# ETHERNET.net
KiCad netlist of a schematic drawn in Altium Designer
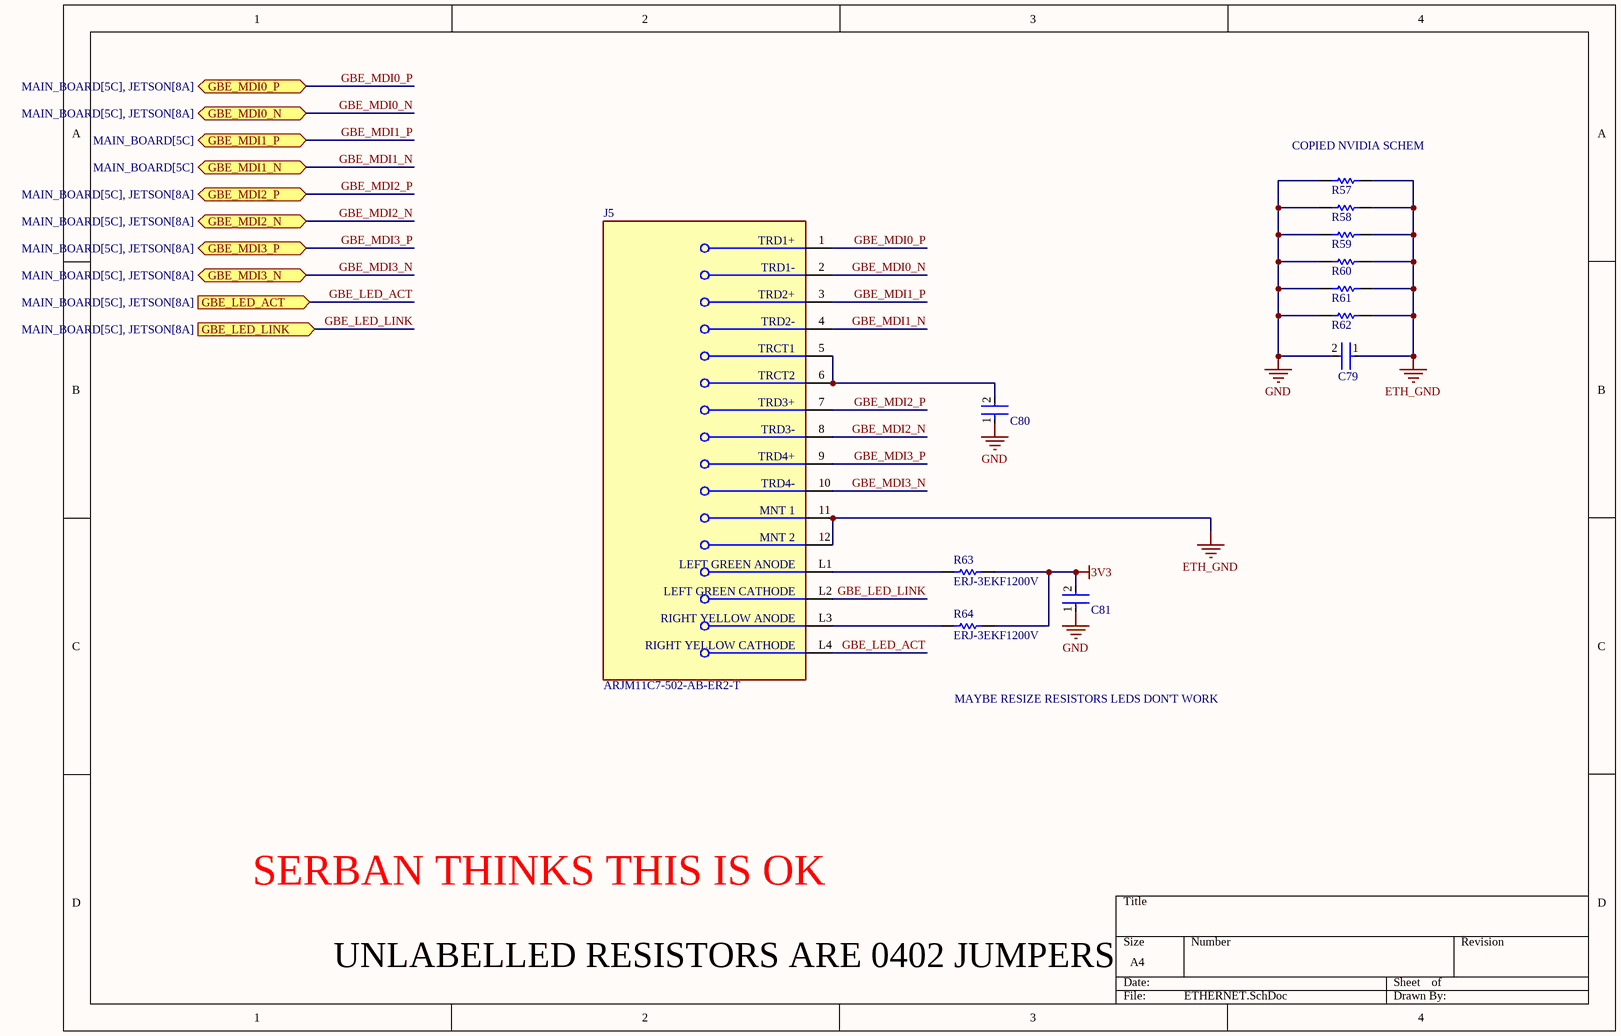
[diagram p0: ETHERNET.SchDoc]

(export (version "E")
  (design (tool "Eeschema 10.0.6"))
  (components
    (comp (ref "C79")
      (value "C1005X7R1H104K050BB")
      (footprint "FP-C1005-050-0_05-IPC_C")
      (description "Multilayer Ceramic Capacitors 100nF ±10% 50V X7R SMD 0402")
      (fields (field (name "VOLTAGE") "50V") (field (name "TOLERANCE") "10%"))
      (libsource (lib "Altium Content Vault") (part "b4654b650e69147ec39a6b967a45e02"))
    )
    (comp (ref "C80")
      (value "C1005X7R1H104K050BB")
      (footprint "FP-C1005-050-0_05-IPC_C")
      (description "Multilayer Ceramic Capacitors 100nF ±10% 50V X7R SMD 0402")
      (fields (field (name "VOLTAGE") "50V") (field (name "TOLERANCE") "10%"))
      (libsource (lib "Altium Content Vault") (part "b4654b650e69147ec39a6b967a45e02"))
    )
    (comp (ref "C81")
      (value "C1005X7R1H104K050BB")
      (footprint "FP-C1005-050-0_05-IPC_C")
      (description "Multilayer Ceramic Capacitors 100nF ±10% 50V X7R SMD 0402")
      (fields (field (name "VOLTAGE") "50V") (field (name "TOLERANCE") "10%"))
      (libsource (lib "Altium Content Vault") (part "b4654b650e69147ec39a6b967a45e02"))
    )
    (comp (ref "J5")
      (value "ARJM11C7-502-AB-ER2-T")
      (footprint "FP-ARJM11C7-502-AB-ER2-T-MFG")
      (description "RJ45 JACK W/MAG 1X1 1000BASE-T")
      (fields
        (field (name "MANUFACTURER") "Abracon")
        (field (name "OCTOPART") "https://octopart.com/arjm11c7-502-ab-er2-t-abracon-86945316")
      )
      (libsource (lib "Altium Content Vault") (part "c9e9675df30893a1b3e4105448caa83"))
    )
    (comp (ref "R57")
      (value "0402 JUMPER 0 OHM")
      (footprint "RESC1005X40X25NL05T05")
      (description "READ THE NAME")
      (libsource (lib "uORocketry Hardware") (part "RES"))
    )
    (comp (ref "R58")
      (value "0402 JUMPER 0 OHM")
      (footprint "RESC1005X40X25NL05T05")
      (description "READ THE NAME")
      (libsource (lib "uORocketry Hardware") (part "RES"))
    )
    (comp (ref "R59")
      (value "0402 JUMPER 0 OHM")
      (footprint "RESC1005X40X25NL05T05")
      (description "READ THE NAME")
      (libsource (lib "uORocketry Hardware") (part "RES"))
    )
    (comp (ref "R60")
      (value "0402 JUMPER 0 OHM")
      (footprint "RESC1005X40X25NL05T05")
      (description "READ THE NAME")
      (libsource (lib "uORocketry Hardware") (part "RES"))
    )
    (comp (ref "R61")
      (value "0402 JUMPER 0 OHM")
      (footprint "RESC1005X40X25NL05T05")
      (description "READ THE NAME")
      (libsource (lib "uORocketry Hardware") (part "RES"))
    )
    (comp (ref "R62")
      (value "0402 JUMPER 0 OHM")
      (footprint "RESC1005X40X25NL05T05")
      (description "READ THE NAME")
      (libsource (lib "uORocketry Hardware") (part "RES"))
    )
    (comp (ref "R63")
      (value "ERJ-3EKF1200V")
      (footprint "RESC1609X55X30ML15T15")
      (description "Chip Resistor, 120 Ohm, +/- 1%, 0.1 W, -55 to 155 degC, 0603 (1608 Metric), RoHS, Tape and Reel")
      (fields (field (name "TOLERANCE") "1%") (field (name "MANUFACTURER") "Panasonic"))
      (libsource (lib "Altium Content Vault") (part "RES-2"))
    )
    (comp (ref "R64")
      (value "ERJ-3EKF1200V")
      (footprint "RESC1609X55X30ML15T15")
      (description "Chip Resistor, 120 Ohm, +/- 1%, 0.1 W, -55 to 155 degC, 0603 (1608 Metric), RoHS, Tape and Reel")
      (fields (field (name "TOLERANCE") "1%") (field (name "MANUFACTURER") "Panasonic"))
      (libsource (lib "Altium Content Vault") (part "RES-2"))
    )
  )
  (nets
    (net (code "1") (name "/GBE_LED_ACT") (class "Default")
      (node (ref "J5") (pin "L4") (pinfunction "RIGHT_YELLOW_CATHODE_L4") (pintype "passive"))
    )
    (net (code "2") (name "/GBE_LED_LINK") (class "Default")
      (node (ref "J5") (pin "L2") (pinfunction "LEFT_GREEN_CATHODE_L2") (pintype "passive"))
    )
    (net (code "3") (name "/GBE_MDI0_N") (class "Default")
      (node (ref "J5") (pin "2") (pinfunction "TRD1-_2") (pintype "passive"))
    )
    (net (code "4") (name "/GBE_MDI0_P") (class "Default")
      (node (ref "J5") (pin "1") (pinfunction "TRD1+_1") (pintype "passive"))
    )
    (net (code "5") (name "/GBE_MDI1_N") (class "Default")
      (node (ref "J5") (pin "4") (pinfunction "TRD2-_4") (pintype "passive"))
    )
    (net (code "6") (name "/GBE_MDI1_P") (class "Default")
      (node (ref "J5") (pin "3") (pinfunction "TRD2+_3") (pintype "passive"))
    )
    (net (code "7") (name "/GBE_MDI2_N") (class "Default")
      (node (ref "J5") (pin "8") (pinfunction "TRD3-_8") (pintype "passive"))
    )
    (net (code "8") (name "/GBE_MDI2_P") (class "Default")
      (node (ref "J5") (pin "7") (pinfunction "TRD3+_7") (pintype "passive"))
    )
    (net (code "9") (name "/GBE_MDI3_N") (class "Default")
      (node (ref "J5") (pin "10") (pinfunction "TRD4-_10") (pintype "passive"))
    )
    (net (code "10") (name "/GBE_MDI3_P") (class "Default")
      (node (ref "J5") (pin "9") (pinfunction "TRD4+_9") (pintype "passive"))
    )
    (net (code "11") (name "3V3") (class "Default")
      (node (ref "C81") (pin "2") (pinfunction "2_2") (pintype "passive"))
      (node (ref "R63") (pin "2") (pinfunction "2_2") (pintype "passive"))
      (node (ref "R64") (pin "2") (pinfunction "2_2") (pintype "passive"))
    )
    (net (code "12") (name "ETH_GND") (class "Default")
      (node (ref "C79") (pin "1") (pinfunction "1_1") (pintype "passive"))
      (node (ref "J5") (pin "11") (pinfunction "MNT_1_11") (pintype "passive"))
      (node (ref "J5") (pin "12") (pinfunction "MNT_2_12") (pintype "passive"))
      (node (ref "R57") (pin "2") (pinfunction "2_2") (pintype "passive"))
      (node (ref "R58") (pin "2") (pinfunction "2_2") (pintype "passive"))
      (node (ref "R59") (pin "2") (pinfunction "2_2") (pintype "passive"))
      (node (ref "R60") (pin "2") (pinfunction "2_2") (pintype "passive"))
      (node (ref "R61") (pin "2") (pinfunction "2_2") (pintype "passive"))
      (node (ref "R62") (pin "2") (pinfunction "2_2") (pintype "passive"))
    )
    (net (code "13") (name "GND") (class "Default")
      (node (ref "C79") (pin "2") (pinfunction "2_2") (pintype "passive"))
      (node (ref "C80") (pin "1") (pinfunction "1_1") (pintype "passive"))
      (node (ref "C81") (pin "1") (pinfunction "1_1") (pintype "passive"))
      (node (ref "R57") (pin "1") (pinfunction "1_1") (pintype "passive"))
      (node (ref "R58") (pin "1") (pinfunction "1_1") (pintype "passive"))
      (node (ref "R59") (pin "1") (pinfunction "1_1") (pintype "passive"))
      (node (ref "R60") (pin "1") (pinfunction "1_1") (pintype "passive"))
      (node (ref "R61") (pin "1") (pinfunction "1_1") (pintype "passive"))
      (node (ref "R62") (pin "1") (pinfunction "1_1") (pintype "passive"))
    )
    (net (code "14") (name "Net-(J5-LEFT_GREEN_ANODE)") (class "Default")
      (node (ref "J5") (pin "L1") (pinfunction "LEFT_GREEN_ANODE_L1") (pintype "passive"))
      (node (ref "R63") (pin "1") (pinfunction "1_1") (pintype "passive"))
    )
    (net (code "15") (name "Net-(J5-RIGHT_YELLOW_ANODE)") (class "Default")
      (node (ref "J5") (pin "L3") (pinfunction "RIGHT_YELLOW_ANODE_L3") (pintype "passive"))
      (node (ref "R64") (pin "1") (pinfunction "1_1") (pintype "passive"))
    )
    (net (code "16") (name "Net-(J5-TRCT1)") (class "Default")
      (node (ref "C80") (pin "2") (pinfunction "2_2") (pintype "passive"))
      (node (ref "J5") (pin "5") (pinfunction "TRCT1_5") (pintype "passive"))
      (node (ref "J5") (pin "6") (pinfunction "TRCT2_6") (pintype "passive"))
    )
  )
)
